# rf-power.net
KiCad netlist of a schematic drawn in EAGLE
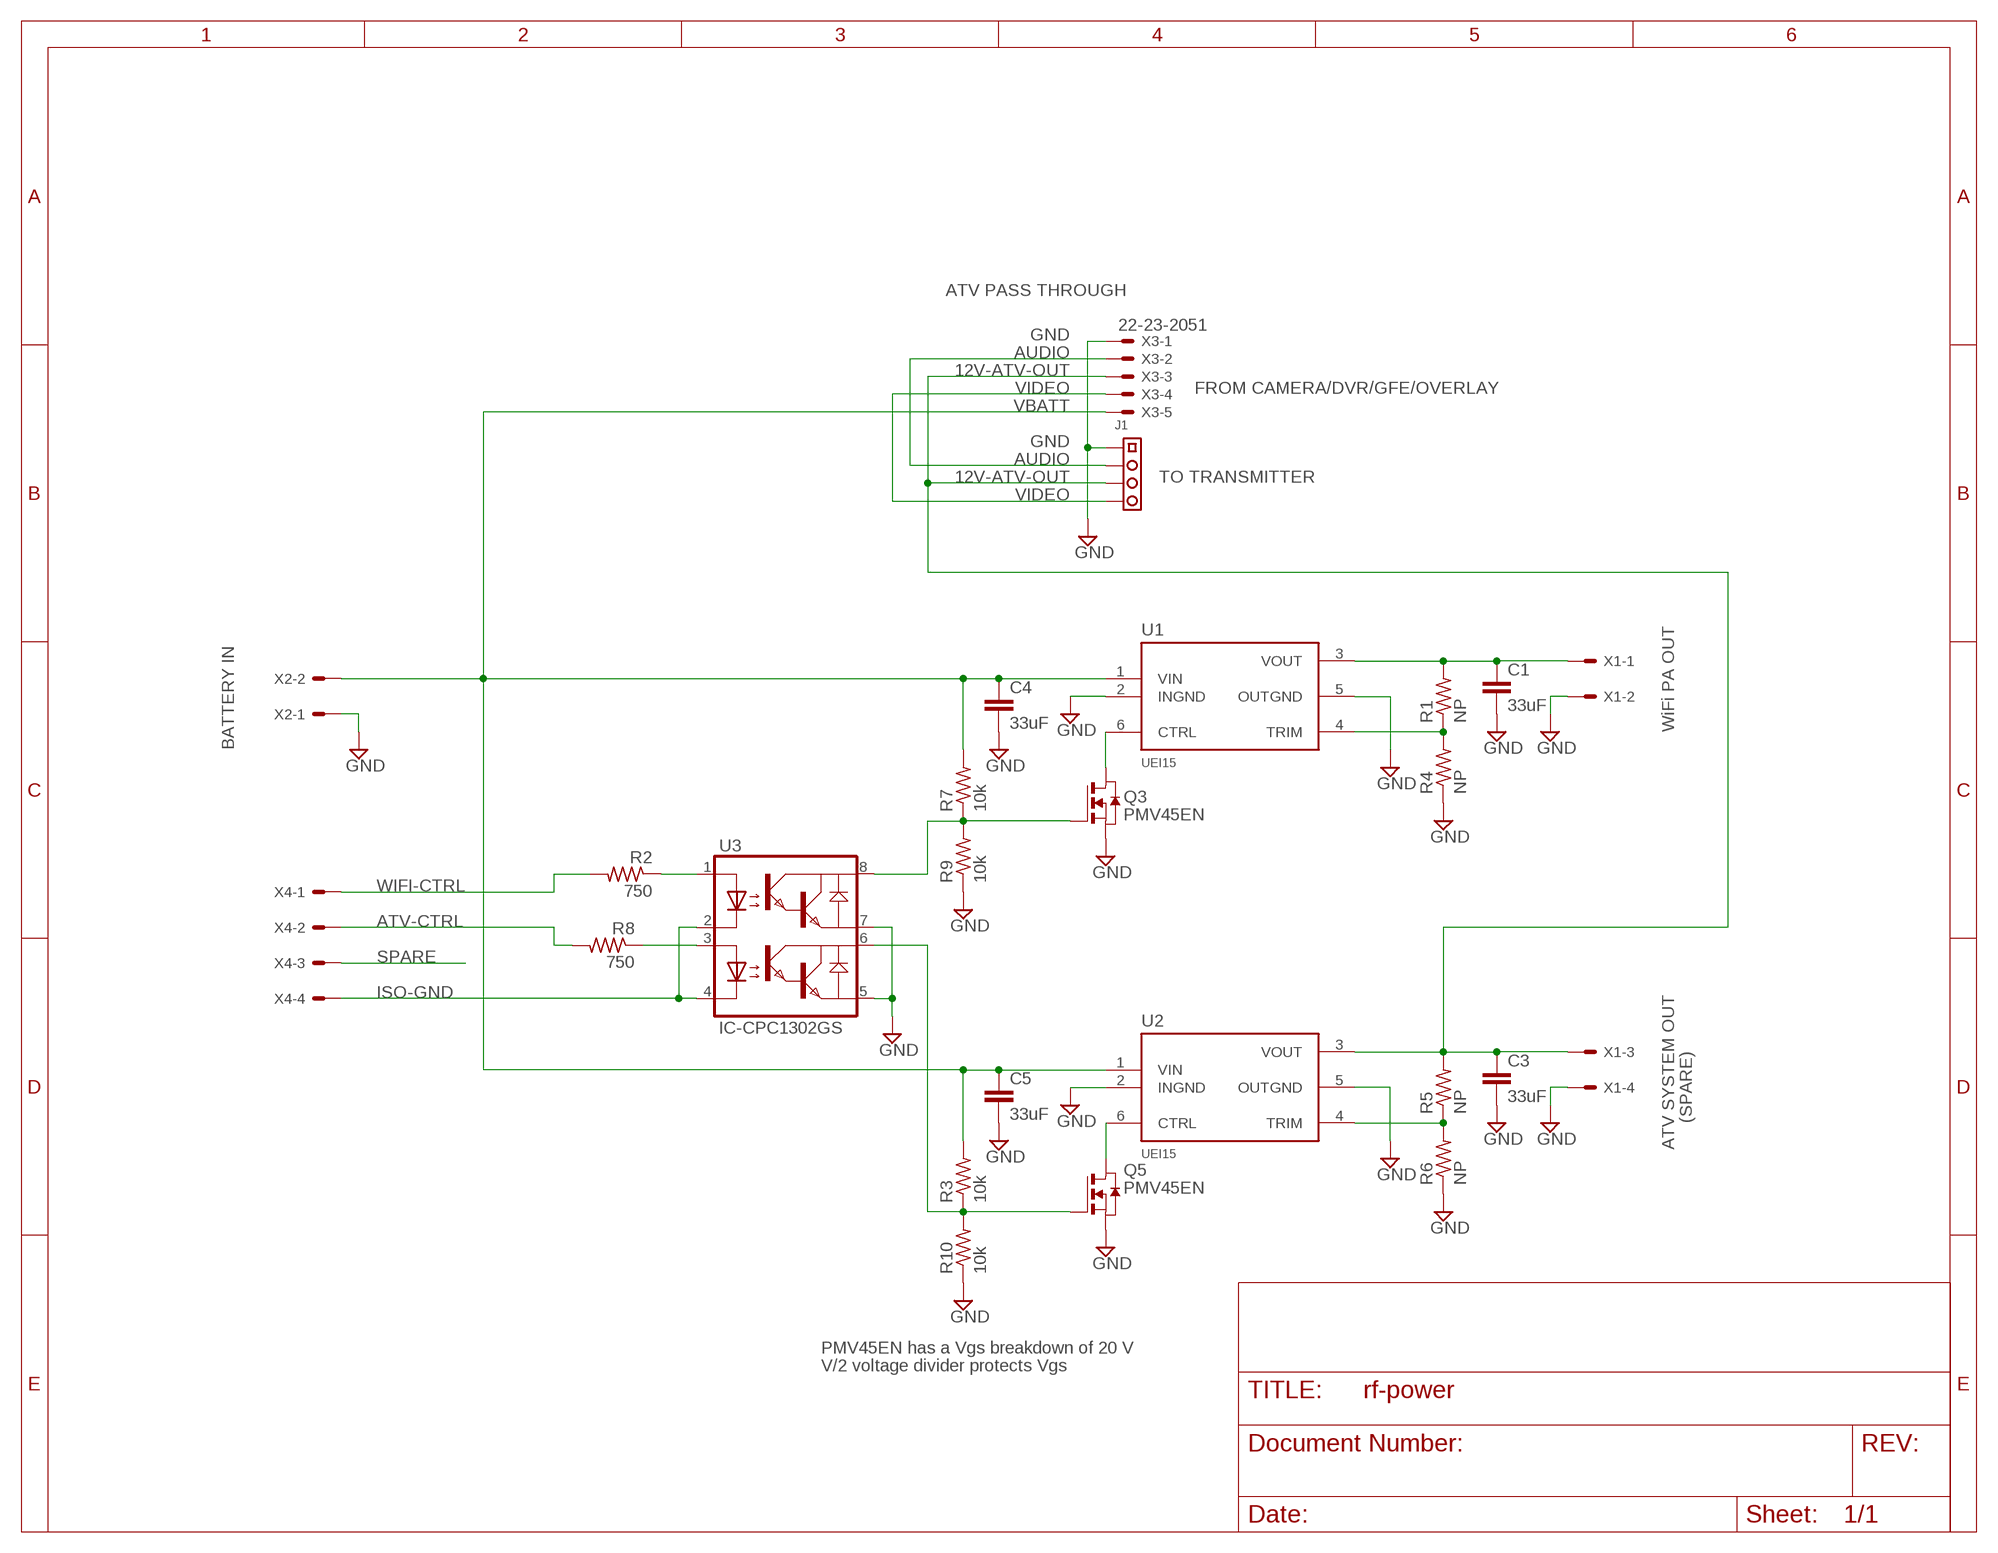
[diagram p0: schematic, sheet 1]

(export (version "E")
  (design (tool "Eeschema 10.0.6"))
  (components
    (comp (ref "C1")
      (value "33uF")
      (footprint "eagle-import:1206-B")
      (libsource (lib "eagle-import") (part "C-EU1206-B"))
    )
    (comp (ref "C3")
      (value "33uF")
      (footprint "eagle-import:1206-B")
      (libsource (lib "eagle-import") (part "C-EU1206-B"))
    )
    (comp (ref "C4")
      (value "33uF")
      (footprint "eagle-import:1206-B")
      (libsource (lib "eagle-import") (part "C-EU1206-B"))
    )
    (comp (ref "C5")
      (value "33uF")
      (footprint "eagle-import:1206-B")
      (libsource (lib "eagle-import") (part "C-EU1206-B"))
    )
    (comp (ref "J1")
      (value "CON-2MM-4X1")
      (footprint "eagle-import:2MM-4X1")
      (libsource (lib "eagle-import") (part "CON-2MM-4X1"))
    )
    (comp (ref "Q3")
      (value "PMV45EN")
      (footprint "eagle-import:SOT23")
      (libsource (lib "eagle-import") (part "PMV45EN"))
    )
    (comp (ref "Q5")
      (value "PMV45EN")
      (footprint "eagle-import:SOT23")
      (libsource (lib "eagle-import") (part "PMV45EN"))
    )
    (comp (ref "R1")
      (value "NP")
      (footprint "eagle-import:0805-C-NOSILK")
      (libsource (lib "eagle-import") (part "R-US_0805-C-NOSILK"))
    )
    (comp (ref "R2")
      (value "750")
      (footprint "eagle-import:0805-C-NOSILK")
      (libsource (lib "eagle-import") (part "R-US_0805-C-NOSILK"))
    )
    (comp (ref "R3")
      (value "10k")
      (footprint "eagle-import:0805-C-NOSILK")
      (libsource (lib "eagle-import") (part "R-US_0805-C-NOSILK"))
    )
    (comp (ref "R4")
      (value "NP")
      (footprint "eagle-import:0805-C-NOSILK")
      (libsource (lib "eagle-import") (part "R-US_0805-C-NOSILK"))
    )
    (comp (ref "R5")
      (value "NP")
      (footprint "eagle-import:0805-C-NOSILK")
      (libsource (lib "eagle-import") (part "R-US_0805-C-NOSILK"))
    )
    (comp (ref "R6")
      (value "NP")
      (footprint "eagle-import:0805-C-NOSILK")
      (libsource (lib "eagle-import") (part "R-US_0805-C-NOSILK"))
    )
    (comp (ref "R7")
      (value "10k")
      (footprint "eagle-import:0805-C-NOSILK")
      (libsource (lib "eagle-import") (part "R-US_0805-C-NOSILK"))
    )
    (comp (ref "R8")
      (value "750")
      (footprint "eagle-import:0805-C-NOSILK")
      (libsource (lib "eagle-import") (part "R-US_0805-C-NOSILK"))
    )
    (comp (ref "R9")
      (value "10k")
      (footprint "eagle-import:0805-C-NOSILK")
      (libsource (lib "eagle-import") (part "R-US_0805-C-NOSILK"))
    )
    (comp (ref "R10")
      (value "10k")
      (footprint "eagle-import:0805-C-NOSILK")
      (libsource (lib "eagle-import") (part "R-US_0805-C-NOSILK"))
    )
    (comp (ref "U1")
      (value "UEI15")
      (footprint "eagle-import:UEI15_PIN")
      (libsource (lib "eagle-import") (part "UEI15"))
    )
    (comp (ref "U2")
      (value "UEI15")
      (footprint "eagle-import:UEI15_PIN")
      (libsource (lib "eagle-import") (part "UEI15"))
    )
    (comp (ref "U3")
      (value "IC-CPC1302GS")
      (footprint "eagle-import:DIL-SMT-8")
      (libsource (lib "eagle-import") (part "IC-CPC1302GS"))
    )
    (comp (ref "X1")
      (value "22-23-2041")
      (footprint "eagle-import:22-23-2041")
      (fields
        (field (name "MF") "MOLEX")
        (field (name "MF_1") "MOLEX")
        (field (name "MPN") "22-23-2041")
        (field (name "OC_FARNELL") "1462920")
        (field (name "OC_NEWARK") "38C0355")
      )
      (libsource (lib "eagle-import") (part "22-23-2041"))
    )
    (comp (ref "X2")
      (value "22-23-2021")
      (footprint "eagle-import:22-23-2021")
      (fields
        (field (name "MF") "MOLEX")
        (field (name "MF_1") "MOLEX")
        (field (name "MPN") "22-23-2021")
        (field (name "OC_FARNELL") "1462926")
        (field (name "OC_NEWARK") "25C3832")
      )
      (libsource (lib "eagle-import") (part "22-23-2021"))
    )
    (comp (ref "X3")
      (value "22-23-2051")
      (footprint "eagle-import:22-23-2051")
      (fields (field (name "MF") "MOLEX"))
      (libsource (lib "eagle-import") (part "22-23-2051"))
    )
    (comp (ref "X4")
      (value "22-23-2041")
      (footprint "eagle-import:22-23-2041")
      (fields
        (field (name "MF") "MOLEX")
        (field (name "MF_1") "MOLEX")
        (field (name "MPN") "22-23-2041")
        (field (name "OC_FARNELL") "1462920")
        (field (name "OC_NEWARK") "38C0355")
      )
      (libsource (lib "eagle-import") (part "22-23-2041"))
    )
  )
  (nets
    (net (code "1") (name "/12V-ATV-OUT") (class "Default")
      (node (ref "C3") (pin "1") (pinfunction "1_1") (pintype "passive"))
      (node (ref "J1") (pin "3") (pinfunction "3_3") (pintype "passive"))
      (node (ref "R5") (pin "2") (pinfunction "2_2") (pintype "passive"))
      (node (ref "U2") (pin "3") (pinfunction "VOUT_3") (pintype "bidirectional"))
      (node (ref "X1") (pin "3") (pinfunction "S_3") (pintype "passive"))
      (node (ref "X3") (pin "3") (pinfunction "S_3") (pintype "passive"))
    )
    (net (code "2") (name "/ATV-CTRL") (class "Default")
      (node (ref "R8") (pin "2") (pinfunction "2_2") (pintype "passive"))
      (node (ref "X4") (pin "2") (pinfunction "S_2") (pintype "passive"))
    )
    (net (code "3") (name "/AUDIO") (class "Default")
      (node (ref "J1") (pin "2") (pinfunction "2_2") (pintype "passive"))
      (node (ref "X3") (pin "2") (pinfunction "S_2") (pintype "passive"))
    )
    (net (code "4") (name "/ISO-GND") (class "Default")
      (node (ref "U3") (pin "2") (pinfunction "K1_2") (pintype "passive"))
      (node (ref "U3") (pin "4") (pinfunction "K2_4") (pintype "passive"))
      (node (ref "X4") (pin "4") (pinfunction "S_4") (pintype "passive"))
    )
    (net (code "5") (name "/SPARE") (class "Default")
      (node (ref "X4") (pin "3") (pinfunction "S_3") (pintype "passive"))
    )
    (net (code "6") (name "/VBATT") (class "Default")
      (node (ref "C4") (pin "1") (pinfunction "1_1") (pintype "passive"))
      (node (ref "C5") (pin "1") (pinfunction "1_1") (pintype "passive"))
      (node (ref "R3") (pin "2") (pinfunction "2_2") (pintype "passive"))
      (node (ref "R7") (pin "2") (pinfunction "2_2") (pintype "passive"))
      (node (ref "U1") (pin "1") (pinfunction "VIN_1") (pintype "bidirectional"))
      (node (ref "U2") (pin "1") (pinfunction "VIN_1") (pintype "bidirectional"))
      (node (ref "X2") (pin "2") (pinfunction "S_2") (pintype "passive"))
      (node (ref "X3") (pin "5") (pinfunction "S_5") (pintype "passive"))
    )
    (net (code "7") (name "/VIDEO") (class "Default")
      (node (ref "J1") (pin "4") (pinfunction "4_4") (pintype "passive"))
      (node (ref "X3") (pin "4") (pinfunction "S_4") (pintype "passive"))
    )
    (net (code "8") (name "/WIFI-CTRL") (class "Default")
      (node (ref "R2") (pin "2") (pinfunction "2_2") (pintype "passive"))
      (node (ref "X4") (pin "1") (pinfunction "S_1") (pintype "passive"))
    )
    (net (code "9") (name "GND") (class "Default")
      (node (ref "C1") (pin "2") (pinfunction "2_2") (pintype "passive"))
      (node (ref "C3") (pin "2") (pinfunction "2_2") (pintype "passive"))
      (node (ref "C4") (pin "2") (pinfunction "2_2") (pintype "passive"))
      (node (ref "C5") (pin "2") (pinfunction "2_2") (pintype "passive"))
      (node (ref "J1") (pin "1") (pinfunction "1_1") (pintype "passive"))
      (node (ref "Q3") (pin "2") (pinfunction "S_2") (pintype "passive"))
      (node (ref "Q5") (pin "2") (pinfunction "S_2") (pintype "passive"))
      (node (ref "R10") (pin "1") (pinfunction "1_1") (pintype "passive"))
      (node (ref "R4") (pin "1") (pinfunction "1_1") (pintype "passive"))
      (node (ref "R6") (pin "1") (pinfunction "1_1") (pintype "passive"))
      (node (ref "R9") (pin "1") (pinfunction "1_1") (pintype "passive"))
      (node (ref "U1") (pin "2") (pinfunction "INGND_2") (pintype "bidirectional"))
      (node (ref "U1") (pin "5") (pinfunction "OUTGND_5") (pintype "bidirectional"))
      (node (ref "U2") (pin "2") (pinfunction "INGND_2") (pintype "bidirectional"))
      (node (ref "U2") (pin "5") (pinfunction "OUTGND_5") (pintype "bidirectional"))
      (node (ref "U3") (pin "5") (pinfunction "E2_5") (pintype "passive"))
      (node (ref "U3") (pin "7") (pinfunction "E1_7") (pintype "passive"))
      (node (ref "X1") (pin "2") (pinfunction "S_2") (pintype "passive"))
      (node (ref "X1") (pin "4") (pinfunction "S_4") (pintype "passive"))
      (node (ref "X2") (pin "1") (pinfunction "S_1") (pintype "passive"))
      (node (ref "X3") (pin "1") (pinfunction "S_1") (pintype "passive"))
    )
    (net (code "10") (name "Net-(Q3-D)") (class "Default")
      (node (ref "Q3") (pin "3") (pinfunction "D_3") (pintype "passive"))
      (node (ref "U1") (pin "6") (pinfunction "CTRL_6") (pintype "bidirectional"))
    )
    (net (code "11") (name "Net-(Q3-G)") (class "Default")
      (node (ref "Q3") (pin "1") (pinfunction "G_1") (pintype "passive"))
      (node (ref "R7") (pin "1") (pinfunction "1_1") (pintype "passive"))
      (node (ref "R9") (pin "2") (pinfunction "2_2") (pintype "passive"))
      (node (ref "U3") (pin "8") (pinfunction "C1_8") (pintype "passive"))
    )
    (net (code "12") (name "Net-(Q5-D)") (class "Default")
      (node (ref "Q5") (pin "3") (pinfunction "D_3") (pintype "passive"))
      (node (ref "U2") (pin "6") (pinfunction "CTRL_6") (pintype "bidirectional"))
    )
    (net (code "13") (name "Net-(Q5-G)") (class "Default")
      (node (ref "Q5") (pin "1") (pinfunction "G_1") (pintype "passive"))
      (node (ref "R10") (pin "2") (pinfunction "2_2") (pintype "passive"))
      (node (ref "R3") (pin "1") (pinfunction "1_1") (pintype "passive"))
      (node (ref "U3") (pin "6") (pinfunction "C2_6") (pintype "passive"))
    )
    (net (code "14") (name "Net-(U1-TRIM)") (class "Default")
      (node (ref "R1") (pin "1") (pinfunction "1_1") (pintype "passive"))
      (node (ref "R4") (pin "2") (pinfunction "2_2") (pintype "passive"))
      (node (ref "U1") (pin "4") (pinfunction "TRIM_4") (pintype "bidirectional"))
    )
    (net (code "15") (name "Net-(U1-VOUT)") (class "Default")
      (node (ref "C1") (pin "1") (pinfunction "1_1") (pintype "passive"))
      (node (ref "R1") (pin "2") (pinfunction "2_2") (pintype "passive"))
      (node (ref "U1") (pin "3") (pinfunction "VOUT_3") (pintype "bidirectional"))
      (node (ref "X1") (pin "1") (pinfunction "S_1") (pintype "passive"))
    )
    (net (code "16") (name "Net-(U2-TRIM)") (class "Default")
      (node (ref "R5") (pin "1") (pinfunction "1_1") (pintype "passive"))
      (node (ref "R6") (pin "2") (pinfunction "2_2") (pintype "passive"))
      (node (ref "U2") (pin "4") (pinfunction "TRIM_4") (pintype "bidirectional"))
    )
    (net (code "17") (name "Net-(U3-A1)") (class "Default")
      (node (ref "R2") (pin "1") (pinfunction "1_1") (pintype "passive"))
      (node (ref "U3") (pin "1") (pinfunction "A1_1") (pintype "passive"))
    )
    (net (code "18") (name "Net-(U3-A2)") (class "Default")
      (node (ref "R8") (pin "1") (pinfunction "1_1") (pintype "passive"))
      (node (ref "U3") (pin "3") (pinfunction "A2_3") (pintype "passive"))
    )
  )
)
